# RF.net
KiCad netlist of a schematic drawn in Altium Designer
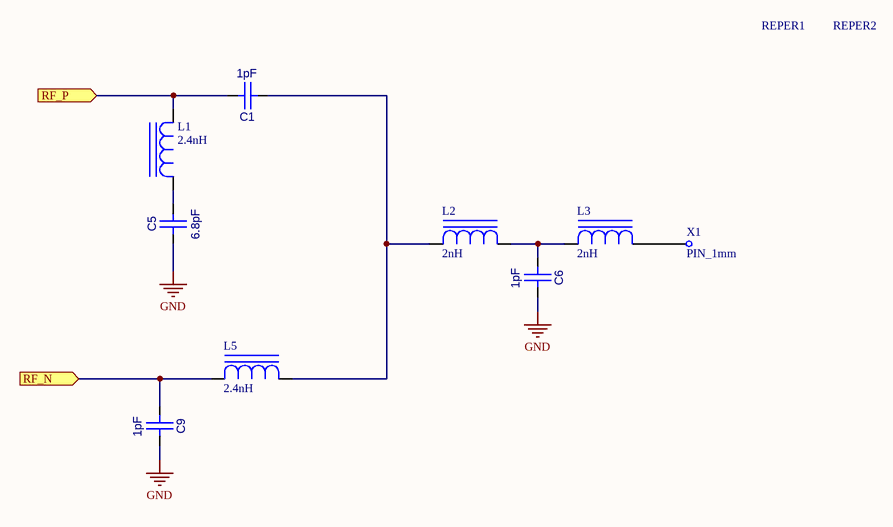
[diagram p0: RF.SchDoc]

(export (version "E")
  (design (tool "Eeschema 10.0.6"))
  (components
    (comp (ref "C1")
      (value "1pF")
      (footprint "CC0603")
      (description "CC0603")
      (libsource (lib "gprs_modem_2") (part "CC0603"))
    )
    (comp (ref "C5")
      (value "6.8pF")
      (footprint "CC0603")
      (description "CC0603")
      (libsource (lib "gprs_modem_2") (part "CC0603"))
    )
    (comp (ref "C6")
      (value "1pF")
      (footprint "CC0603")
      (description "CC0603")
      (libsource (lib "gprs_modem_2") (part "CC0603"))
    )
    (comp (ref "C9")
      (value "1pF")
      (footprint "CC0603")
      (description "CC0603")
      (libsource (lib "gprs_modem_2") (part "CC0603"))
    )
    (comp (ref "L1")
      (value "2.4nH")
      (footprint "L0402")
      (description "L0402")
      (libsource (lib "gprs_modem_2") (part "L0402"))
    )
    (comp (ref "L2")
      (value "2nH")
      (footprint "L0402")
      (description "L0402")
      (libsource (lib "gprs_modem_2") (part "L0402"))
    )
    (comp (ref "L3")
      (value "2nH")
      (footprint "L0402")
      (description "L0402")
      (libsource (lib "gprs_modem_2") (part "L0402"))
    )
    (comp (ref "L5")
      (value "2.4nH")
      (footprint "L0402")
      (description "L0402")
      (libsource (lib "gprs_modem_2") (part "L0402"))
    )
    (comp (ref "REPER1")
      (value "REPER1.2")
      (footprint "REPER1.2")
      (libsource (lib "gprs_modem_2") (part "REPER1.2"))
    )
    (comp (ref "REPER2")
      (value "REPER1.2")
      (footprint "REPER1.2")
      (libsource (lib "gprs_modem_2") (part "REPER1.2"))
    )
    (comp (ref "X1")
      (value "PIN_1mm")
      (footprint "PIN_1mm")
      (libsource (lib "gprs_modem_2") (part "PIN_1mm"))
    )
  )
  (nets
    (net (code "1") (name "/RF_N") (class "Default")
      (node (ref "C9") (pin "1") (pinfunction "A_1") (pintype "passive"))
      (node (ref "L5") (pin "1") (pinfunction "A_1") (pintype "passive"))
    )
    (net (code "2") (name "/RF_P") (class "Default")
      (node (ref "C1") (pin "2") (pinfunction "B_2") (pintype "passive"))
      (node (ref "L1") (pin "2") (pinfunction "C_2") (pintype "passive"))
    )
    (net (code "3") (name "GND") (class "Default")
      (node (ref "C5") (pin "1") (pinfunction "A_1") (pintype "passive"))
      (node (ref "C6") (pin "2") (pinfunction "B_2") (pintype "passive"))
      (node (ref "C9") (pin "2") (pinfunction "B_2") (pintype "passive"))
    )
    (net (code "4") (name "Net-(C1-A)") (class "Default")
      (node (ref "C1") (pin "1") (pinfunction "A_1") (pintype "passive"))
      (node (ref "L2") (pin "1") (pinfunction "A_1") (pintype "passive"))
      (node (ref "L5") (pin "2") (pinfunction "C_2") (pintype "passive"))
    )
    (net (code "5") (name "Net-(C5-B)") (class "Default")
      (node (ref "C5") (pin "2") (pinfunction "B_2") (pintype "passive"))
      (node (ref "L1") (pin "1") (pinfunction "A_1") (pintype "passive"))
    )
    (net (code "6") (name "Net-(C6-A)") (class "Default")
      (node (ref "C6") (pin "1") (pinfunction "A_1") (pintype "passive"))
      (node (ref "L2") (pin "2") (pinfunction "C_2") (pintype "passive"))
      (node (ref "L3") (pin "1") (pinfunction "A_1") (pintype "passive"))
    )
    (net (code "7") (name "Net-(L3-C)") (class "Default")
      (node (ref "L3") (pin "2") (pinfunction "C_2") (pintype "passive"))
      (node (ref "X1") (pin "1") (pinfunction "1_1") (pintype "passive"))
    )
    (net (code "8") (name "unconnected-(REPER1-Pad1)") (class "Default")
      (node (ref "REPER1") (pin "1") (pintype "passive"))
    )
    (net (code "9") (name "unconnected-(REPER2-Pad1)") (class "Default")
      (node (ref "REPER2") (pin "1") (pintype "passive"))
    )
  )
)
